# board_012518.net
KiCad netlist of a schematic drawn in EAGLE
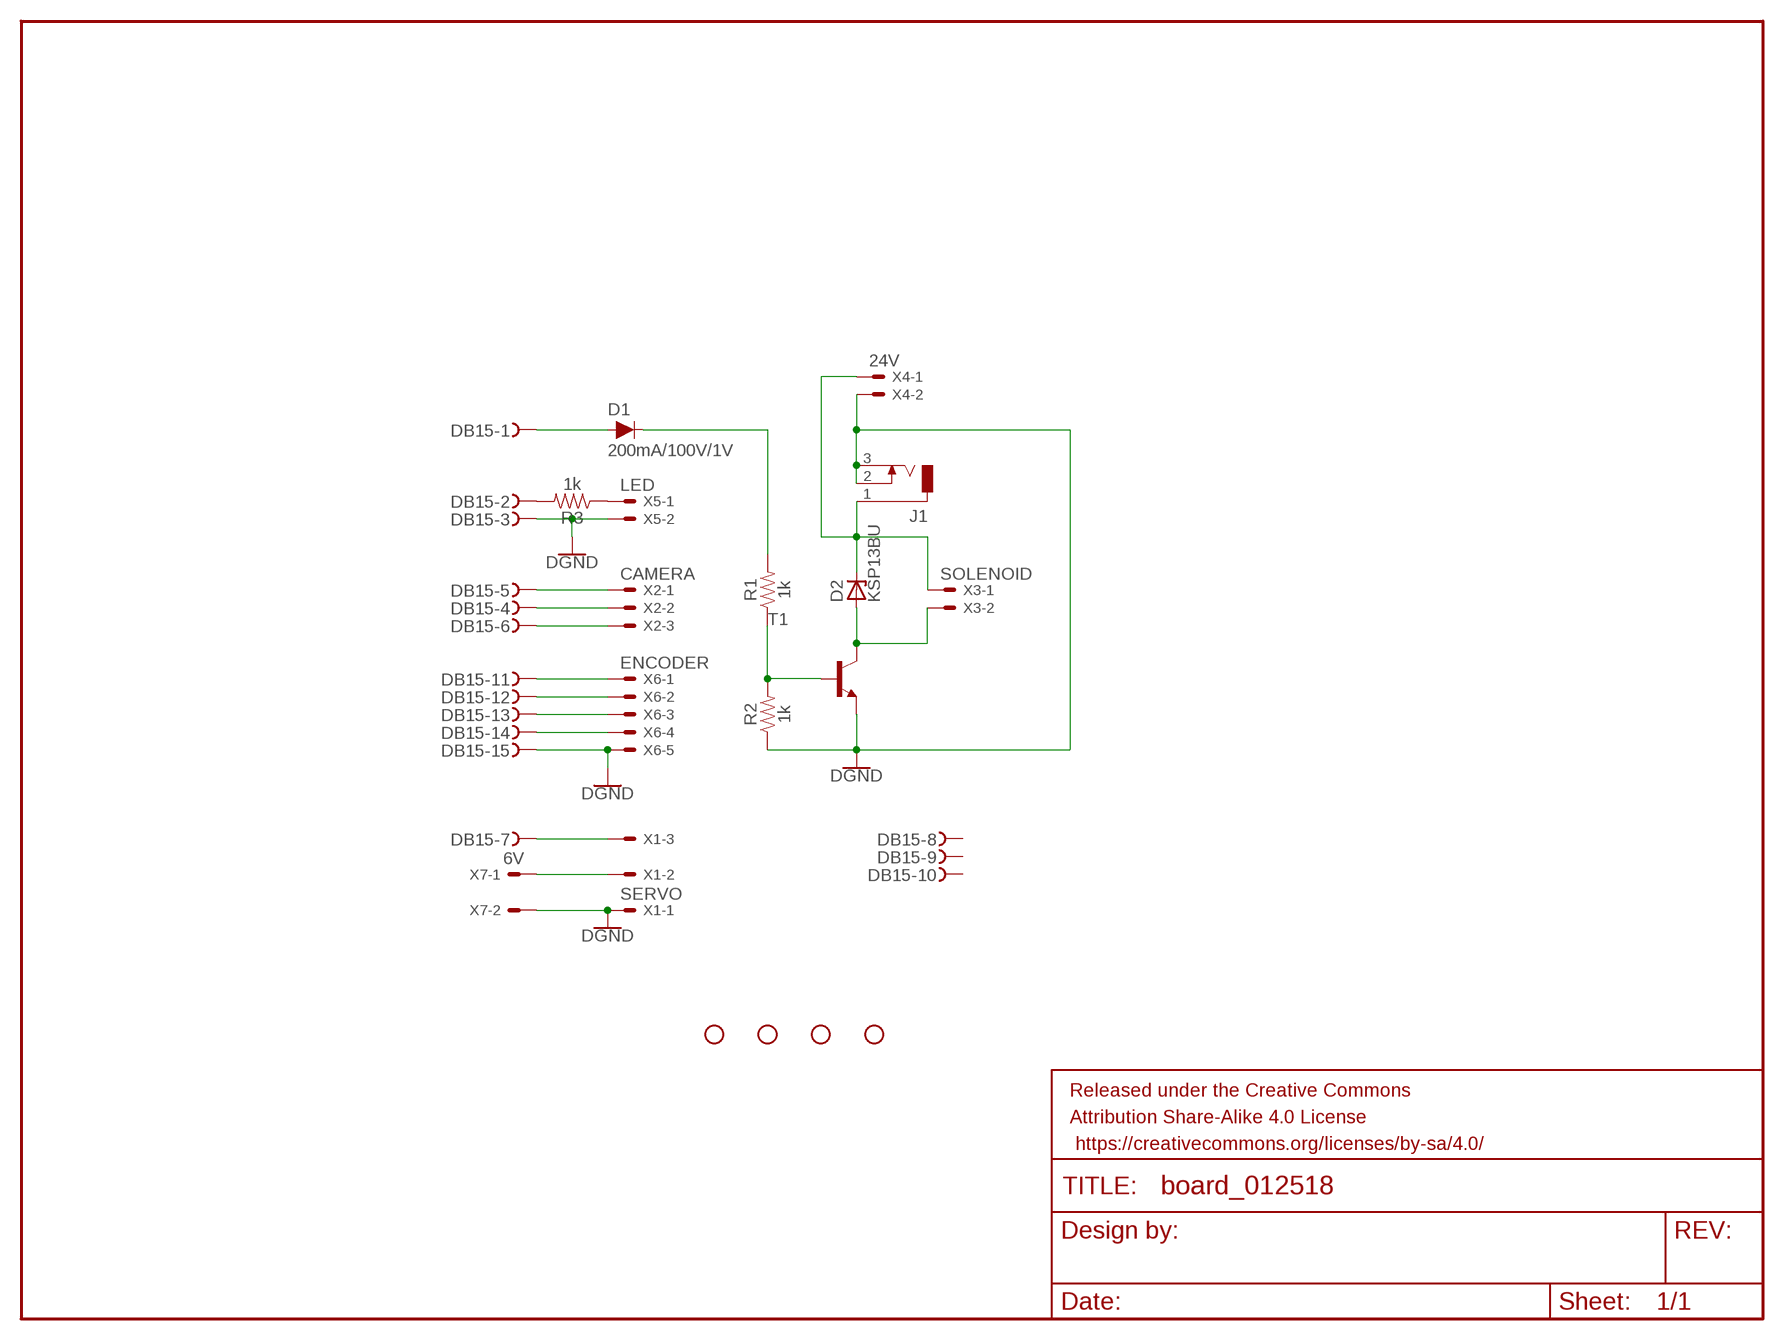
[diagram p0: schematic, sheet 1]

(export (version "E")
  (design (tool "Eeschema 10.0.6"))
  (components
    (comp (ref "D1")
      (value "200mA/100V/1V")
      (footprint "eagle-import:DIODE-1N4148")
      (libsource (lib "eagle-import") (part "DIODE-1N4148"))
    )
    (comp (ref "D2")
      (value "KSP13BU")
      (footprint "eagle-import:P1Z12")
      (libsource (lib "eagle-import") (part "ZENER-DIODEP1-12"))
    )
    (comp (ref "DB15")
      (value "D-SUB15-HDR15RA")
      (footprint "eagle-import:HDR15RA")
      (libsource (lib "eagle-import") (part "D-SUB15-HDR15RA"))
    )
    (comp (ref "FRAME1")
      (value "FRAME-LETTER")
      (footprint "eagle-import:CREATIVE_COMMONS")
      (libsource (lib "eagle-import") (part "FRAME-LETTER"))
    )
    (comp (ref "H1")
      (value "STAND-OFF")
      (footprint "eagle-import:STAND-OFF")
      (libsource (lib "eagle-import") (part "STAND-OFF"))
    )
    (comp (ref "H2")
      (value "STAND-OFF")
      (footprint "eagle-import:STAND-OFF")
      (libsource (lib "eagle-import") (part "STAND-OFF"))
    )
    (comp (ref "H3")
      (value "STAND-OFF")
      (footprint "eagle-import:STAND-OFF")
      (libsource (lib "eagle-import") (part "STAND-OFF"))
    )
    (comp (ref "H4")
      (value "STAND-OFF")
      (footprint "eagle-import:STAND-OFF")
      (libsource (lib "eagle-import") (part "STAND-OFF"))
    )
    (comp (ref "J1")
      (value "DCJ0303")
      (footprint "eagle-import:DCJ0303")
      (libsource (lib "eagle-import") (part "DCJ0303"))
    )
    (comp (ref "R1")
      (value "1k")
      (footprint "eagle-import:AXIAL-0.3")
      (libsource (lib "eagle-import") (part "1KOHM-HORIZ-1/4W-1%"))
    )
    (comp (ref "R2")
      (value "1k")
      (footprint "eagle-import:AXIAL-0.3")
      (libsource (lib "eagle-import") (part "1KOHM-HORIZ-1/4W-1%"))
    )
    (comp (ref "R3")
      (value "1k")
      (footprint "eagle-import:AXIAL-0.3")
      (libsource (lib "eagle-import") (part "1KOHM-HORIZ-1/4W-1%"))
    )
    (comp (ref "T1")
      (value "MPSA13-NPN-TO92-EBC")
      (footprint "eagle-import:TO92-EBC")
      (libsource (lib "eagle-import") (part "-NPN-TO92-EBCMPSA13"))
    )
    (comp (ref "X1")
      (value "SERVO")
      (footprint "eagle-import:70553-03")
      (fields (field (name "MF") "MOLEX"))
      (libsource (lib "eagle-import") (part "C-GRID-03-70553"))
    )
    (comp (ref "X2")
      (value "CAMERA")
      (footprint "eagle-import:70553-03")
      (fields (field (name "MF") "MOLEX"))
      (libsource (lib "eagle-import") (part "C-GRID-03-70553"))
    )
    (comp (ref "X3")
      (value "SOLENOID")
      (footprint "eagle-import:70553-02")
      (fields (field (name "MF") "MOLEX"))
      (libsource (lib "eagle-import") (part "C-GRID-02-70553"))
    )
    (comp (ref "X4")
      (value "24V")
      (footprint "eagle-import:70553-02")
      (fields (field (name "MF") "MOLEX"))
      (libsource (lib "eagle-import") (part "C-GRID-02-70553"))
    )
    (comp (ref "X5")
      (value "LED")
      (footprint "eagle-import:70553-02")
      (fields (field (name "MF") "MOLEX"))
      (libsource (lib "eagle-import") (part "C-GRID-02-70553"))
    )
    (comp (ref "X6")
      (value "ENCODER")
      (footprint "eagle-import:70553-05")
      (fields (field (name "MF") "MOLEX"))
      (libsource (lib "eagle-import") (part "C-GRID-05-70553"))
    )
    (comp (ref "X7")
      (value "6V")
      (footprint "eagle-import:70553-02")
      (fields (field (name "MF") "MOLEX"))
      (libsource (lib "eagle-import") (part "C-GRID-02-70553"))
    )
  )
  (nets
    (net (code "1") (name "DGND") (class "Default")
      (node (ref "DB15") (pin "15") (pinfunction "F_15") (pintype "passive"))
      (node (ref "DB15") (pin "3") (pinfunction "F_3") (pintype "passive"))
      (node (ref "J1") (pin "2") (pinfunction "2_2") (pintype "passive"))
      (node (ref "J1") (pin "3") (pinfunction "3_3") (pintype "passive"))
      (node (ref "R2") (pin "P$1") (pinfunction "1_P$1") (pintype "passive"))
      (node (ref "T1") (pin "E") (pinfunction "E_E") (pintype "passive"))
      (node (ref "X1") (pin "1") (pinfunction "S_1") (pintype "passive"))
      (node (ref "X4") (pin "2") (pinfunction "S_2") (pintype "passive"))
      (node (ref "X5") (pin "2") (pinfunction "S_2") (pintype "passive"))
      (node (ref "X6") (pin "5") (pinfunction "S_5") (pintype "passive"))
      (node (ref "X7") (pin "2") (pinfunction "S_2") (pintype "passive"))
    )
    (net (code "2") (name "Net-(DB15A-F)") (class "Default")
      (node (ref "D1") (pin "A") (pinfunction "A_A") (pintype "passive"))
      (node (ref "DB15") (pin "1") (pinfunction "F_1") (pintype "passive"))
    )
    (net (code "3") (name "Net-(DB15C-F)") (class "Default")
      (node (ref "DB15") (pin "11") (pinfunction "F_11") (pintype "passive"))
      (node (ref "X6") (pin "1") (pinfunction "S_1") (pintype "passive"))
    )
    (net (code "4") (name "Net-(DB15D-F)") (class "Default")
      (node (ref "DB15") (pin "12") (pinfunction "F_12") (pintype "passive"))
      (node (ref "X6") (pin "2") (pinfunction "S_2") (pintype "passive"))
    )
    (net (code "5") (name "Net-(DB15E-F)") (class "Default")
      (node (ref "DB15") (pin "13") (pinfunction "F_13") (pintype "passive"))
      (node (ref "X6") (pin "3") (pinfunction "S_3") (pintype "passive"))
    )
    (net (code "6") (name "Net-(DB15F-F)") (class "Default")
      (node (ref "DB15") (pin "14") (pinfunction "F_14") (pintype "passive"))
      (node (ref "X6") (pin "4") (pinfunction "S_4") (pintype "passive"))
    )
    (net (code "7") (name "Net-(DB15H-F)") (class "Default")
      (node (ref "DB15") (pin "2") (pinfunction "F_2") (pintype "passive"))
      (node (ref "R3") (pin "P$2") (pinfunction "2_P$2") (pintype "passive"))
    )
    (net (code "8") (name "Net-(DB15J-F)") (class "Default")
      (node (ref "DB15") (pin "4") (pinfunction "F_4") (pintype "passive"))
      (node (ref "X2") (pin "2") (pinfunction "S_2") (pintype "passive"))
    )
    (net (code "9") (name "Net-(DB15K-F)") (class "Default")
      (node (ref "DB15") (pin "5") (pinfunction "F_5") (pintype "passive"))
      (node (ref "X2") (pin "1") (pinfunction "S_1") (pintype "passive"))
    )
    (net (code "10") (name "Net-(DB15L-F)") (class "Default")
      (node (ref "DB15") (pin "6") (pinfunction "F_6") (pintype "passive"))
      (node (ref "X2") (pin "3") (pinfunction "S_3") (pintype "passive"))
    )
    (net (code "11") (name "Net-(DB15M-F)") (class "Default")
      (node (ref "DB15") (pin "7") (pinfunction "F_7") (pintype "passive"))
      (node (ref "X1") (pin "3") (pinfunction "S_3") (pintype "passive"))
    )
    (net (code "12") (name "Net-(R1-1)") (class "Default")
      (node (ref "R1") (pin "P$1") (pinfunction "1_P$1") (pintype "passive"))
      (node (ref "R2") (pin "P$2") (pinfunction "2_P$2") (pintype "passive"))
      (node (ref "T1") (pin "B") (pinfunction "B_B") (pintype "passive"))
    )
    (net (code "13") (name "Net-(R1-2)") (class "Default")
      (node (ref "D1") (pin "C") (pinfunction "C_C") (pintype "passive"))
      (node (ref "R1") (pin "P$2") (pinfunction "2_P$2") (pintype "passive"))
    )
    (net (code "14") (name "Net-(R3-1)") (class "Default")
      (node (ref "R3") (pin "P$1") (pinfunction "1_P$1") (pintype "passive"))
      (node (ref "X5") (pin "1") (pinfunction "S_1") (pintype "passive"))
    )
    (net (code "15") (name "Net-(X1B-S)") (class "Default")
      (node (ref "X1") (pin "2") (pinfunction "S_2") (pintype "passive"))
      (node (ref "X7") (pin "1") (pinfunction "S_1") (pintype "passive"))
    )
    (net (code "16") (name "Net-(X3A-S)") (class "Default")
      (node (ref "D2") (pin "C") (pinfunction "C_C") (pintype "passive"))
      (node (ref "J1") (pin "1") (pinfunction "1_1") (pintype "passive"))
      (node (ref "X3") (pin "1") (pinfunction "S_1") (pintype "passive"))
      (node (ref "X4") (pin "1") (pinfunction "S_1") (pintype "passive"))
    )
    (net (code "17") (name "Net-(X3B-S)") (class "Default")
      (node (ref "D2") (pin "A") (pinfunction "A_A") (pintype "passive"))
      (node (ref "T1") (pin "C") (pinfunction "C_C") (pintype "passive"))
      (node (ref "X3") (pin "2") (pinfunction "S_2") (pintype "passive"))
    )
    (net (code "18") (name "unconnected-(DB15B-F-Pad10)") (class "Default")
      (node (ref "DB15") (pin "10") (pinfunction "F_10") (pintype "passive"))
    )
    (net (code "19") (name "unconnected-(DB15N-F-Pad8)") (class "Default")
      (node (ref "DB15") (pin "8") (pinfunction "F_8") (pintype "passive"))
    )
    (net (code "20") (name "unconnected-(DB15O-F-Pad9)") (class "Default")
      (node (ref "DB15") (pin "9") (pinfunction "F_9") (pintype "passive"))
    )
  )
)
